# 1_byte_output.net
KiCad netlist of a schematic drawn in EAGLE
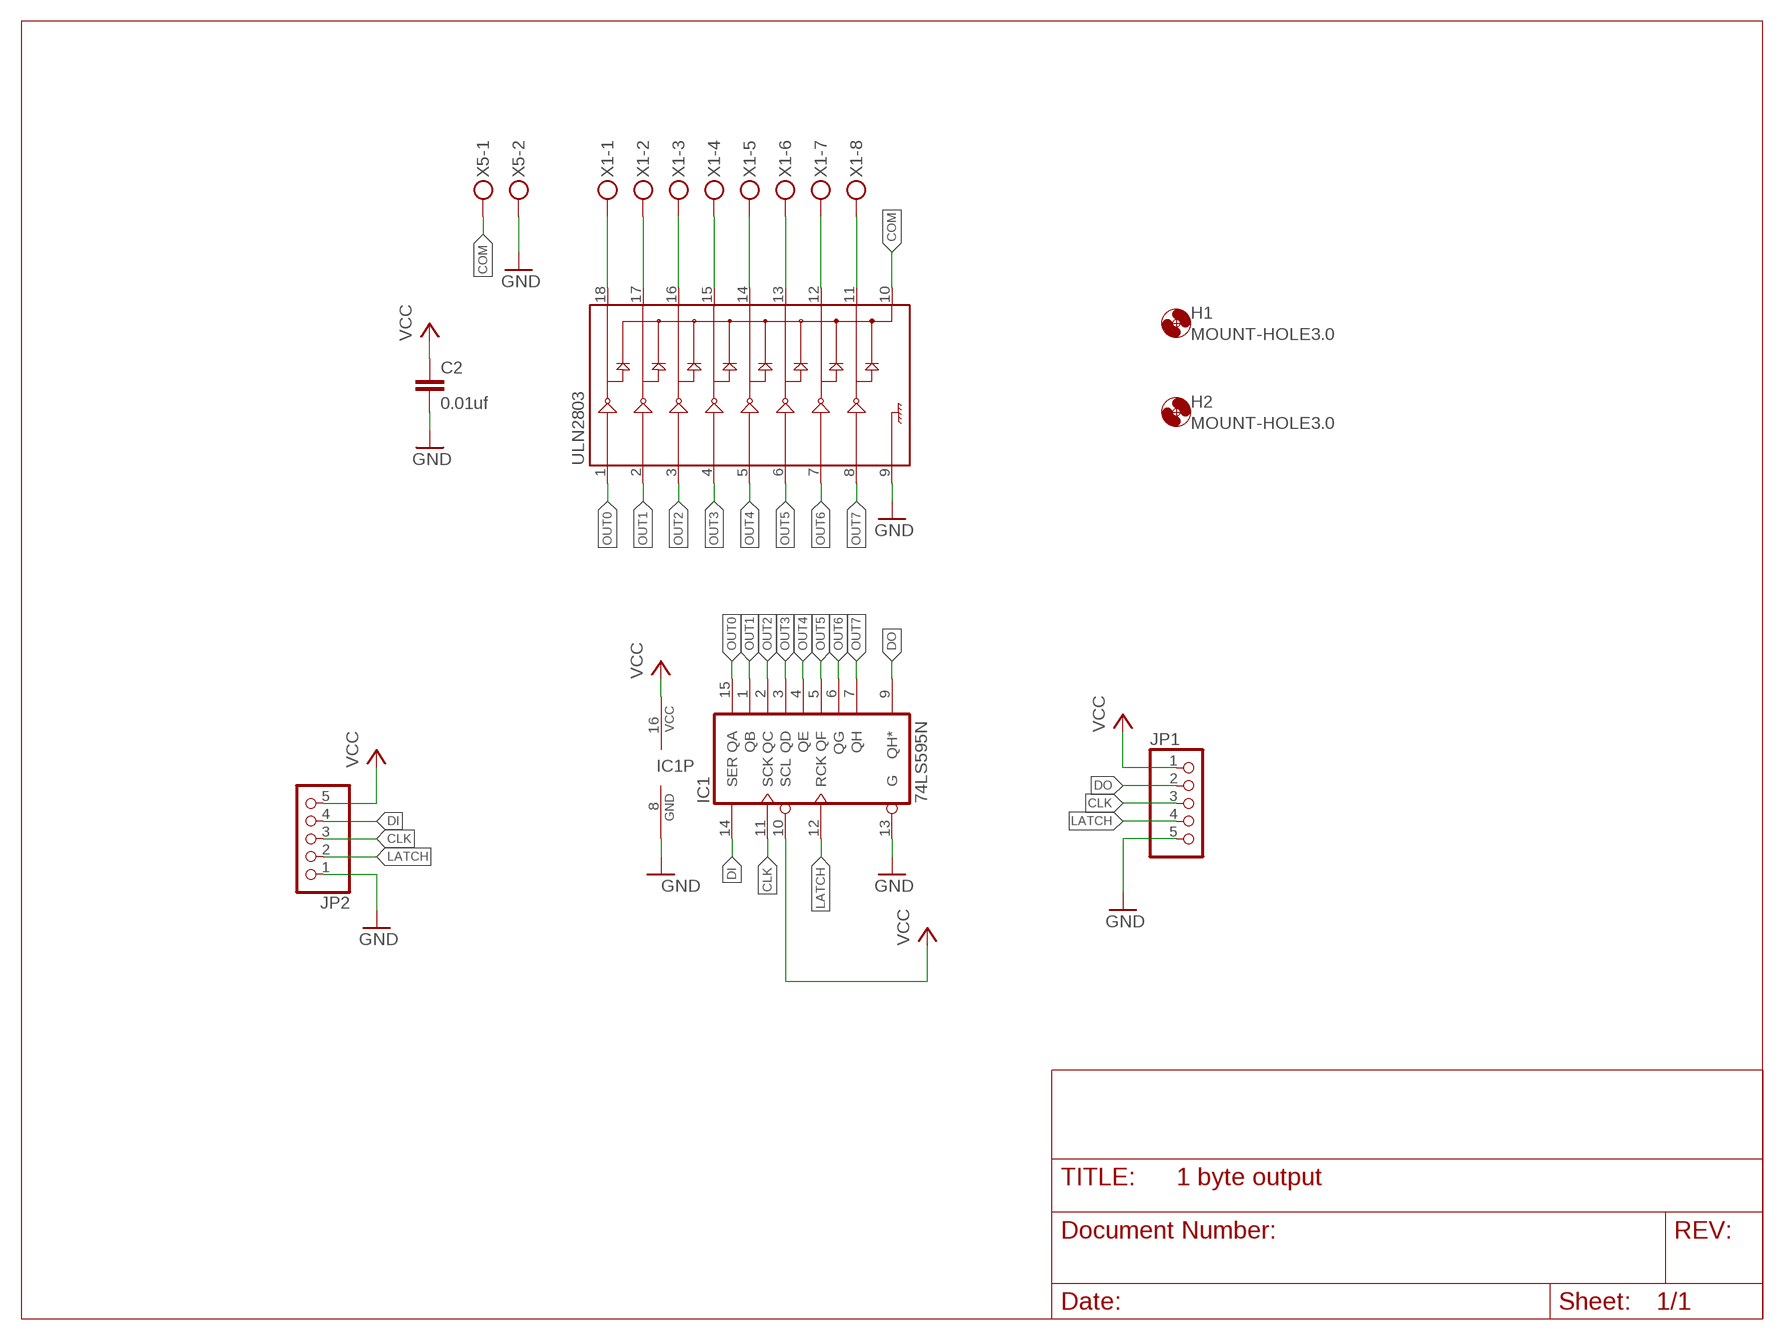
[diagram p0: schematic, sheet 1]

(export (version "E")
  (design (tool "Eeschema 10.0.6"))
  (components
    (comp (ref "C2")
      (value "0.01uf")
      (footprint "eagle-import:C050-035X075")
      (libsource (lib "eagle-import") (part "C-EU050-035X075"))
    )
    (comp (ref "H1")
      (value "MOUNT-HOLE3.0")
      (footprint "eagle-import:3,0")
      (libsource (lib "eagle-import") (part "MOUNT-HOLE3.0"))
    )
    (comp (ref "H2")
      (value "MOUNT-HOLE3.0")
      (footprint "eagle-import:3,0")
      (libsource (lib "eagle-import") (part "MOUNT-HOLE3.0"))
    )
    (comp (ref "IC1")
      (value "74LS595N")
      (footprint "eagle-import:DIL16")
      (libsource (lib "eagle-import") (part "74595NLS"))
    )
    (comp (ref "JP1")
      (value "PINHD-1X5/90")
      (footprint "eagle-import:1X05_90")
      (libsource (lib "eagle-import") (part "PINHD-1X5/90"))
    )
    (comp (ref "JP2")
      (value "PINHD-1X5/90")
      (footprint "eagle-import:1X05_90")
      (libsource (lib "eagle-import") (part "PINHD-1X5/90"))
    )
    (comp (ref "ULN2803")
      (value "ULN2803DIP")
      (footprint "eagle-import:DIL18")
      (libsource (lib "eagle-import") (part "ULN2803DIP"))
    )
    (comp (ref "X1")
      (value "MKDSN1,5/8-5,08")
      (footprint "eagle-import:MKDSN1,5_8-5,08")
      (libsource (lib "eagle-import") (part "MKDSN1,5/8-5,08"))
    )
    (comp (ref "X5")
      (value "MKDSN1,5/2-5,08")
      (footprint "eagle-import:MKDSN1,5_2-5,08")
      (libsource (lib "eagle-import") (part "MKDSN1,5/2-5,08"))
    )
  )
  (nets
    (net (code "1") (name "CLK") (class "Default")
      (node (ref "IC1") (pin "11") (pinfunction "SCK_11") (pintype "input"))
      (node (ref "JP1") (pin "3") (pinfunction "3_3") (pintype "passive"))
      (node (ref "JP2") (pin "3") (pinfunction "3_3") (pintype "passive"))
    )
    (net (code "2") (name "COM") (class "Default")
      (node (ref "ULN2803") (pin "10") (pinfunction "10_10") (pintype "bidirectional"))
      (node (ref "X5") (pin "1") (pinfunction "KL_1") (pintype "passive"))
    )
    (net (code "3") (name "DI") (class "Default")
      (node (ref "IC1") (pin "14") (pinfunction "SER_14") (pintype "input"))
      (node (ref "JP2") (pin "4") (pinfunction "4_4") (pintype "passive"))
    )
    (net (code "4") (name "DO") (class "Default")
      (node (ref "IC1") (pin "9") (pinfunction "QH*_9") (pintype "tri_state"))
      (node (ref "JP1") (pin "2") (pinfunction "2_2") (pintype "passive"))
    )
    (net (code "5") (name "GND") (class "Default")
      (node (ref "C2") (pin "2") (pinfunction "2_2") (pintype "passive"))
      (node (ref "IC1") (pin "13") (pinfunction "G_13") (pintype "input"))
      (node (ref "IC1") (pin "8") (pinfunction "GND_8") (pintype "power_in"))
      (node (ref "JP1") (pin "5") (pinfunction "5_5") (pintype "passive"))
      (node (ref "JP2") (pin "1") (pinfunction "1_1") (pintype "passive"))
      (node (ref "ULN2803") (pin "9") (pinfunction "9_9") (pintype "bidirectional"))
      (node (ref "X5") (pin "2") (pinfunction "KL_2") (pintype "passive"))
    )
    (net (code "6") (name "LATCH") (class "Default")
      (node (ref "IC1") (pin "12") (pinfunction "RCK_12") (pintype "input"))
      (node (ref "JP1") (pin "4") (pinfunction "4_4") (pintype "passive"))
      (node (ref "JP2") (pin "2") (pinfunction "2_2") (pintype "passive"))
    )
    (net (code "7") (name "Net-(X1A-KL)") (class "Default")
      (node (ref "ULN2803") (pin "18") (pinfunction "18_18") (pintype "bidirectional"))
      (node (ref "X1") (pin "1") (pinfunction "KL_1") (pintype "passive"))
    )
    (net (code "8") (name "Net-(X1B-KL)") (class "Default")
      (node (ref "ULN2803") (pin "17") (pinfunction "17_17") (pintype "bidirectional"))
      (node (ref "X1") (pin "2") (pinfunction "KL_2") (pintype "passive"))
    )
    (net (code "9") (name "Net-(X1C-KL)") (class "Default")
      (node (ref "ULN2803") (pin "16") (pinfunction "16_16") (pintype "bidirectional"))
      (node (ref "X1") (pin "3") (pinfunction "KL_3") (pintype "passive"))
    )
    (net (code "10") (name "Net-(X1D-KL)") (class "Default")
      (node (ref "ULN2803") (pin "15") (pinfunction "15_15") (pintype "bidirectional"))
      (node (ref "X1") (pin "4") (pinfunction "KL_4") (pintype "passive"))
    )
    (net (code "11") (name "Net-(X1E-KL)") (class "Default")
      (node (ref "ULN2803") (pin "14") (pinfunction "14_14") (pintype "bidirectional"))
      (node (ref "X1") (pin "5") (pinfunction "KL_5") (pintype "passive"))
    )
    (net (code "12") (name "Net-(X1F-KL)") (class "Default")
      (node (ref "ULN2803") (pin "13") (pinfunction "13_13") (pintype "bidirectional"))
      (node (ref "X1") (pin "6") (pinfunction "KL_6") (pintype "passive"))
    )
    (net (code "13") (name "Net-(X1G-KL)") (class "Default")
      (node (ref "ULN2803") (pin "12") (pinfunction "12_12") (pintype "bidirectional"))
      (node (ref "X1") (pin "7") (pinfunction "KL_7") (pintype "passive"))
    )
    (net (code "14") (name "Net-(X1H-KL)") (class "Default")
      (node (ref "ULN2803") (pin "11") (pinfunction "11_11") (pintype "bidirectional"))
      (node (ref "X1") (pin "8") (pinfunction "KL_8") (pintype "passive"))
    )
    (net (code "15") (name "OUT0") (class "Default")
      (node (ref "IC1") (pin "15") (pinfunction "QA_15") (pintype "tri_state"))
      (node (ref "ULN2803") (pin "1") (pinfunction "1_1") (pintype "bidirectional"))
    )
    (net (code "16") (name "OUT1") (class "Default")
      (node (ref "IC1") (pin "1") (pinfunction "QB_1") (pintype "tri_state"))
      (node (ref "ULN2803") (pin "2") (pinfunction "2_2") (pintype "bidirectional"))
    )
    (net (code "17") (name "OUT2") (class "Default")
      (node (ref "IC1") (pin "2") (pinfunction "QC_2") (pintype "tri_state"))
      (node (ref "ULN2803") (pin "3") (pinfunction "3_3") (pintype "bidirectional"))
    )
    (net (code "18") (name "OUT3") (class "Default")
      (node (ref "IC1") (pin "3") (pinfunction "QD_3") (pintype "tri_state"))
      (node (ref "ULN2803") (pin "4") (pinfunction "4_4") (pintype "bidirectional"))
    )
    (net (code "19") (name "OUT4") (class "Default")
      (node (ref "IC1") (pin "4") (pinfunction "QE_4") (pintype "tri_state"))
      (node (ref "ULN2803") (pin "5") (pinfunction "5_5") (pintype "bidirectional"))
    )
    (net (code "20") (name "OUT5") (class "Default")
      (node (ref "IC1") (pin "5") (pinfunction "QF_5") (pintype "tri_state"))
      (node (ref "ULN2803") (pin "6") (pinfunction "6_6") (pintype "bidirectional"))
    )
    (net (code "21") (name "OUT6") (class "Default")
      (node (ref "IC1") (pin "6") (pinfunction "QG_6") (pintype "tri_state"))
      (node (ref "ULN2803") (pin "7") (pinfunction "7_7") (pintype "bidirectional"))
    )
    (net (code "22") (name "OUT7") (class "Default")
      (node (ref "IC1") (pin "7") (pinfunction "QH_7") (pintype "tri_state"))
      (node (ref "ULN2803") (pin "8") (pinfunction "8_8") (pintype "bidirectional"))
    )
    (net (code "23") (name "VCC") (class "Default")
      (node (ref "C2") (pin "1") (pinfunction "1_1") (pintype "passive"))
      (node (ref "IC1") (pin "10") (pinfunction "SCL_10") (pintype "input"))
      (node (ref "IC1") (pin "16") (pinfunction "VCC_16") (pintype "power_in"))
      (node (ref "JP1") (pin "1") (pinfunction "1_1") (pintype "passive"))
      (node (ref "JP2") (pin "5") (pinfunction "5_5") (pintype "passive"))
    )
  )
)
